# raspberrypi-testcard.net
KiCad netlist of a schematic drawn in EAGLE
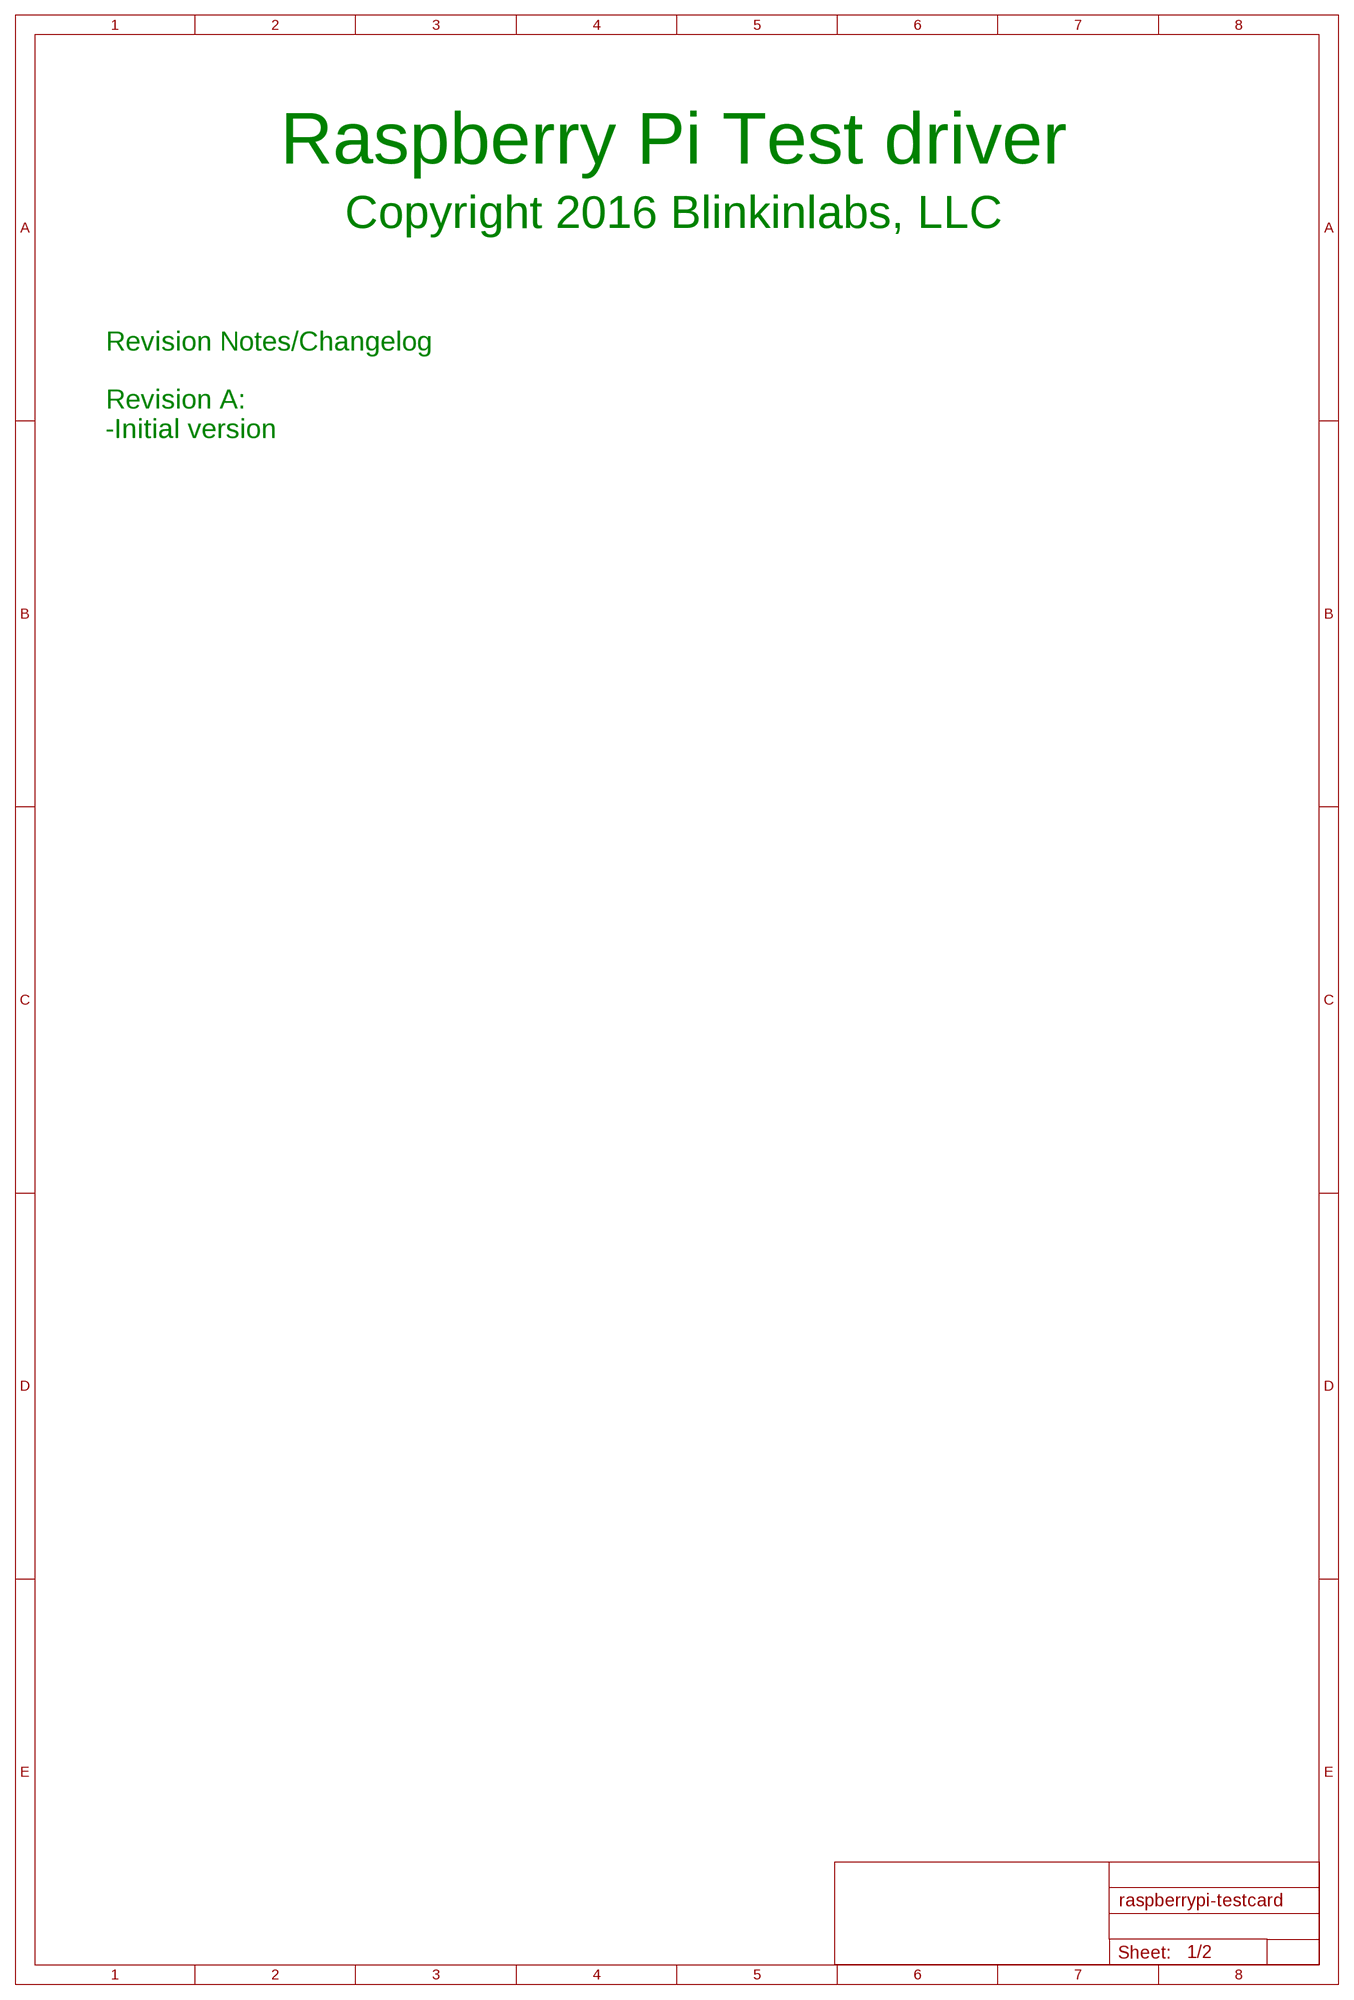
[diagram p0: schematic, sheet 1]
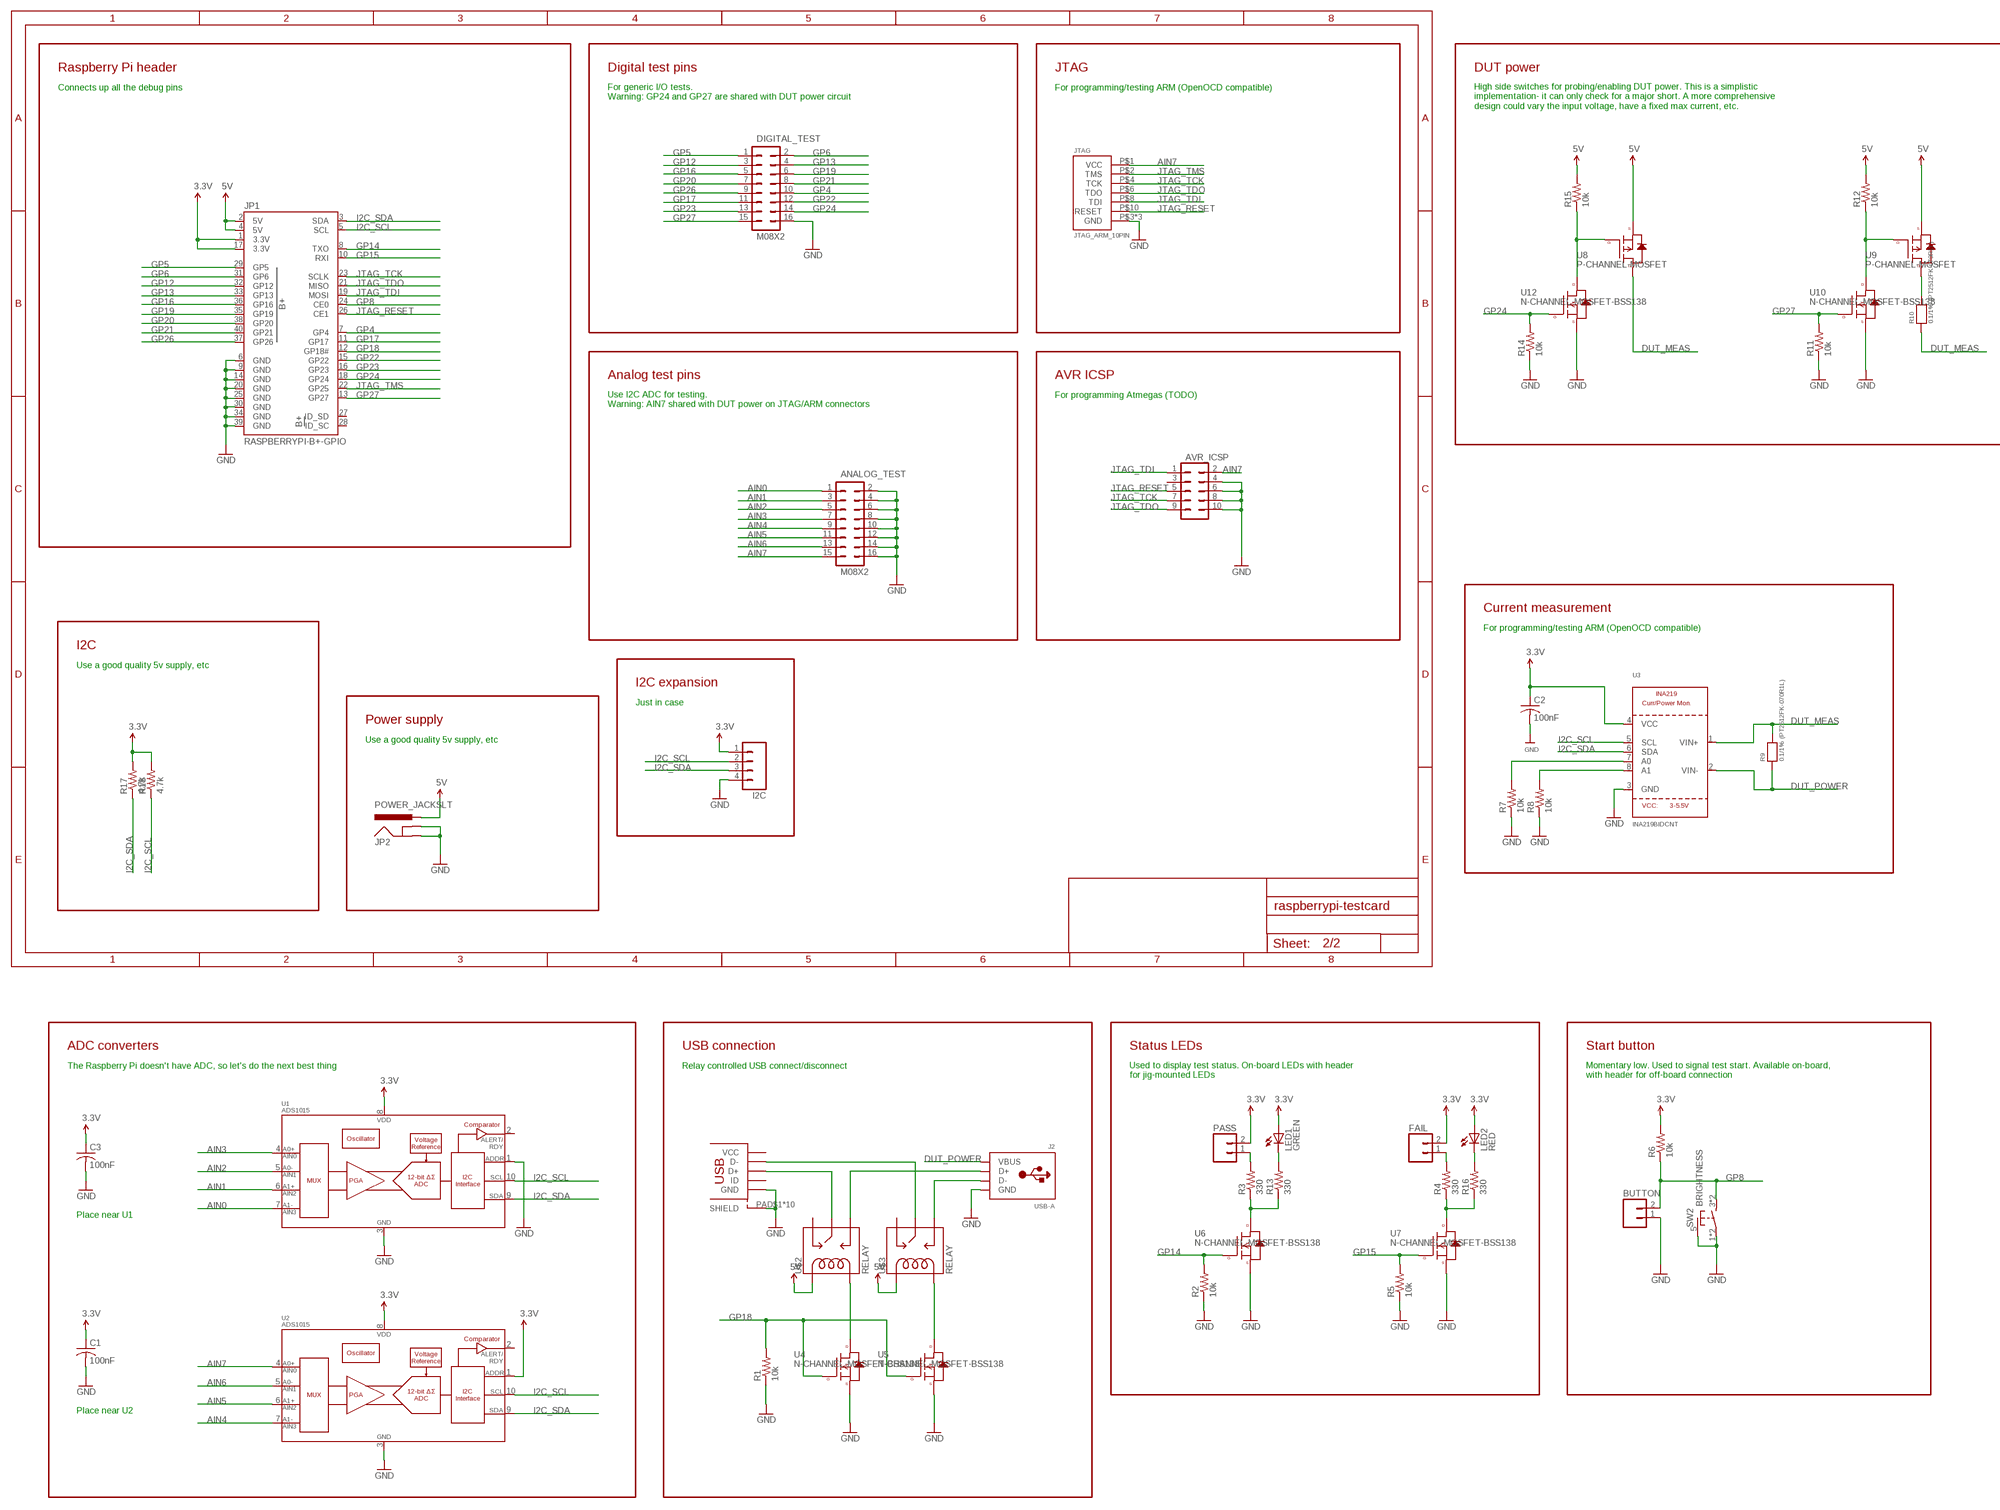
[diagram p1: schematic, sheet 2, part 1 of 2]
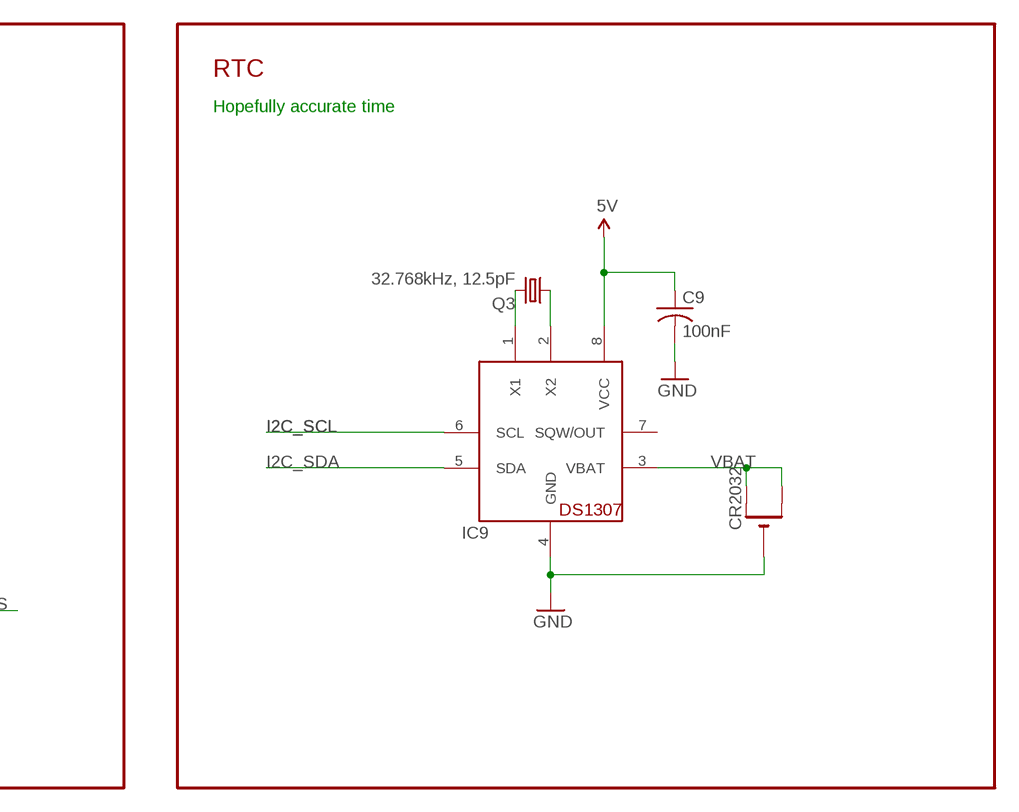
[diagram p2: schematic, sheet 2, part 2 of 2]

(export (version "E")
  (design (tool "Eeschema 10.0.6"))
  (components
    (comp (ref "ANALOG_TEST")
      (value "M08X2")
      (footprint "eagle-import:2X8")
      (libsource (lib "eagle-import") (part "M08X2"))
    )
    (comp (ref "AVR_ICSP")
      (value "M05X2PTH")
      (footprint "eagle-import:AVR_ICSP")
      (libsource (lib "eagle-import") (part "M05X2PTH"))
    )
    (comp (ref "BUTTON")
      (value "M02JST-PTH-2")
      (footprint "eagle-import:JST-2-PTH")
      (libsource (lib "eagle-import") (part "M02JST-PTH-2"))
    )
    (comp (ref "C1")
      (value "100nF")
      (footprint "eagle-import:C0402")
      (libsource (lib "eagle-import") (part "C-USC0402"))
    )
    (comp (ref "C2")
      (value "100nF")
      (footprint "eagle-import:C0402")
      (libsource (lib "eagle-import") (part "C-USC0402"))
    )
    (comp (ref "C3")
      (value "100nF")
      (footprint "eagle-import:C0402")
      (libsource (lib "eagle-import") (part "C-USC0402"))
    )
    (comp (ref "C9")
      (value "100nF")
      (footprint "eagle-import:C0402K")
      (libsource (lib "eagle-import") (part "C-USC0402K"))
    )
    (comp (ref "CR2032")
      (value "CR2032SMT")
      (footprint "eagle-import:CR2032-SMD")
      (libsource (lib "eagle-import") (part "CR2032SMT"))
    )
    (comp (ref "DIGITAL_TEST")
      (value "M08X2")
      (footprint "eagle-import:2X8")
      (libsource (lib "eagle-import") (part "M08X2"))
    )
    (comp (ref "FAIL")
      (value "M02JST-PTH-2")
      (footprint "eagle-import:JST-2-PTH")
      (libsource (lib "eagle-import") (part "M02JST-PTH-2"))
    )
    (comp (ref "I2C")
      (value "M04PTH")
      (footprint "eagle-import:1X04")
      (libsource (lib "eagle-import") (part "M04PTH"))
    )
    (comp (ref "IC9")
      (value "DS1307SO08")
      (footprint "eagle-import:SO08-150")
      (libsource (lib "eagle-import") (part "DS1307SO08"))
    )
    (comp (ref "J1")
      (value "USB_MICROSMT+THRUHULE")
      (footprint "eagle-import:USB_MICRO_THRUHOLE")
      (libsource (lib "eagle-import") (part "USB_MICROSMT+THRUHULE"))
    )
    (comp (ref "J2")
      (value "USB-A")
      (footprint "eagle-import:MOLEX_480371000")
      (libsource (lib "eagle-import") (part "USB-A"))
    )
    (comp (ref "JP1")
      (value "RASPBERRYPI-B+-GPIO")
      (footprint "eagle-import:2X20-SHROUDED")
      (libsource (lib "eagle-import") (part "RASPBERRYPI-B+-GPIO"))
    )
    (comp (ref "JP2")
      (value "POWER_JACKSLT")
      (footprint "eagle-import:POWER_JACK_SLOT")
      (libsource (lib "eagle-import") (part "POWER_JACKSLT"))
    )
    (comp (ref "JTAG")
      (value "JTAG_ARM_10PIN")
      (footprint "eagle-import:2X05-1.27MM-SMD")
      (libsource (lib "eagle-import") (part "JTAG_ARM_10PIN"))
    )
    (comp (ref "LED1")
      (value "GREEN")
      (footprint "eagle-import:CHIP-LED0805")
      (libsource (lib "eagle-import") (part "LEDCHIP-LED0805"))
    )
    (comp (ref "LED2")
      (value "RED")
      (footprint "eagle-import:CHIP-LED0805")
      (libsource (lib "eagle-import") (part "LEDCHIP-LED0805"))
    )
    (comp (ref "PASS")
      (value "M02JST-PTH-2")
      (footprint "eagle-import:JST-2-PTH")
      (libsource (lib "eagle-import") (part "M02JST-PTH-2"))
    )
    (comp (ref "Q3")
      (value "32.768kHz, 12.5pF")
      (footprint "eagle-import:TC26H")
      (libsource (lib "eagle-import") (part "CRYSTALTC26H"))
    )
    (comp (ref "R1")
      (value "10k")
      (footprint "eagle-import:R0402")
      (libsource (lib "eagle-import") (part "R-US_R0402"))
    )
    (comp (ref "R2")
      (value "10k")
      (footprint "eagle-import:R0402")
      (libsource (lib "eagle-import") (part "R-US_R0402"))
    )
    (comp (ref "R3")
      (value "330")
      (footprint "eagle-import:R0402")
      (libsource (lib "eagle-import") (part "R-US_R0402"))
    )
    (comp (ref "R4")
      (value "330")
      (footprint "eagle-import:R0402")
      (libsource (lib "eagle-import") (part "R-US_R0402"))
    )
    (comp (ref "R5")
      (value "10k")
      (footprint "eagle-import:R0402")
      (libsource (lib "eagle-import") (part "R-US_R0402"))
    )
    (comp (ref "R6")
      (value "10k")
      (footprint "eagle-import:R0402")
      (libsource (lib "eagle-import") (part "R-US_R0402"))
    )
    (comp (ref "R7")
      (value "10k")
      (footprint "eagle-import:R0402")
      (libsource (lib "eagle-import") (part "R-US_R0402"))
    )
    (comp (ref "R8")
      (value "10k")
      (footprint "eagle-import:R0402")
      (libsource (lib "eagle-import") (part "R-US_R0402"))
    )
    (comp (ref "R9")
      (value "0.1/1% (PT2512FK-070R1L)")
      (footprint "eagle-import:2512")
      (libsource (lib "eagle-import") (part "RESISTOR2512"))
    )
    (comp (ref "R10")
      (value "0.1/1% (PT2512FK-070R1L)")
      (footprint "eagle-import:2512")
      (libsource (lib "eagle-import") (part "RESISTOR2512"))
    )
    (comp (ref "R11")
      (value "10k")
      (footprint "eagle-import:R0402")
      (libsource (lib "eagle-import") (part "R-US_R0402"))
    )
    (comp (ref "R12")
      (value "10k")
      (footprint "eagle-import:R0402")
      (libsource (lib "eagle-import") (part "R-US_R0402"))
    )
    (comp (ref "R13")
      (value "330")
      (footprint "eagle-import:R0402")
      (libsource (lib "eagle-import") (part "R-US_R0402"))
    )
    (comp (ref "R14")
      (value "10k")
      (footprint "eagle-import:R0402")
      (libsource (lib "eagle-import") (part "R-US_R0402"))
    )
    (comp (ref "R15")
      (value "10k")
      (footprint "eagle-import:R0402")
      (libsource (lib "eagle-import") (part "R-US_R0402"))
    )
    (comp (ref "R16")
      (value "330")
      (footprint "eagle-import:R0402")
      (libsource (lib "eagle-import") (part "R-US_R0402"))
    )
    (comp (ref "R17")
      (value "4.7k")
      (footprint "eagle-import:R0402")
      (libsource (lib "eagle-import") (part "R-US_R0402"))
    )
    (comp (ref "R18")
      (value "4.7k")
      (footprint "eagle-import:R0402")
      (libsource (lib "eagle-import") (part "R-US_R0402"))
    )
    (comp (ref "SW2")
      (value "BRIGHTNESS")
      (footprint "eagle-import:TD-07XB")
      (libsource (lib "eagle-import") (part "BUTTON_MOMENTARY_GROUND"))
    )
    (comp (ref "U$2")
      (value "RELAY")
      (footprint "eagle-import:RELAY_HK23F-5V")
      (libsource (lib "eagle-import") (part "RELAY"))
    )
    (comp (ref "U$3")
      (value "RELAY")
      (footprint "eagle-import:RELAY_HK23F-5V")
      (libsource (lib "eagle-import") (part "RELAY"))
    )
    (comp (ref "U1")
      (value "ADS1015")
      (footprint "eagle-import:MSOP10")
      (libsource (lib "eagle-import") (part "ADS1015"))
    )
    (comp (ref "U2")
      (value "ADS1015")
      (footprint "eagle-import:MSOP10")
      (libsource (lib "eagle-import") (part "ADS1015"))
    )
    (comp (ref "U3")
      (value "INA219BIDCNT")
      (footprint "eagle-import:SOT23-8")
      (libsource (lib "eagle-import") (part "INA219"))
    )
    (comp (ref "U4")
      (value "N-CHANNEL-MOSFET-BSS138")
      (footprint "eagle-import:SOT23-3")
      (libsource (lib "eagle-import") (part "N-CHANNEL-MOSFET-BSS138"))
    )
    (comp (ref "U5")
      (value "N-CHANNEL-MOSFET-BSS138")
      (footprint "eagle-import:SOT23-3")
      (libsource (lib "eagle-import") (part "N-CHANNEL-MOSFET-BSS138"))
    )
    (comp (ref "U6")
      (value "N-CHANNEL-MOSFET-BSS138")
      (footprint "eagle-import:SOT23-3")
      (libsource (lib "eagle-import") (part "N-CHANNEL-MOSFET-BSS138"))
    )
    (comp (ref "U7")
      (value "N-CHANNEL-MOSFET-BSS138")
      (footprint "eagle-import:SOT23-3")
      (libsource (lib "eagle-import") (part "N-CHANNEL-MOSFET-BSS138"))
    )
    (comp (ref "U8")
      (value "P-CHANNEL-MOSFET")
      (footprint "eagle-import:SOT23-3")
      (libsource (lib "eagle-import") (part "P-CHANNEL-MOSFET"))
    )
    (comp (ref "U9")
      (value "P-CHANNEL-MOSFET")
      (footprint "eagle-import:SOT23-3")
      (libsource (lib "eagle-import") (part "P-CHANNEL-MOSFET"))
    )
    (comp (ref "U10")
      (value "N-CHANNEL-MOSFET-BSS138")
      (footprint "eagle-import:SOT23-3")
      (libsource (lib "eagle-import") (part "N-CHANNEL-MOSFET-BSS138"))
    )
    (comp (ref "U12")
      (value "N-CHANNEL-MOSFET-BSS138")
      (footprint "eagle-import:SOT23-3")
      (libsource (lib "eagle-import") (part "N-CHANNEL-MOSFET-BSS138"))
    )
  )
  (nets
    (net (code "1") (name "3.3V") (class "Default")
      (node (ref "C1") (pin "1") (pinfunction "1_1") (pintype "passive"))
      (node (ref "C2") (pin "1") (pinfunction "1_1") (pintype "passive"))
      (node (ref "C3") (pin "1") (pinfunction "1_1") (pintype "passive"))
      (node (ref "FAIL") (pin "2") (pinfunction "2_2") (pintype "passive"))
      (node (ref "I2C") (pin "1") (pinfunction "1_1") (pintype "passive"))
      (node (ref "JP1") (pin "1") (pinfunction "3.3V_1") (pintype "power_in"))
      (node (ref "JP1") (pin "17") (pinfunction "3.3V_17") (pintype "power_in"))
      (node (ref "LED1") (pin "A") (pinfunction "A_A") (pintype "passive"))
      (node (ref "LED2") (pin "A") (pinfunction "A_A") (pintype "passive"))
      (node (ref "PASS") (pin "2") (pinfunction "2_2") (pintype "passive"))
      (node (ref "R17") (pin "2") (pinfunction "2_2") (pintype "passive"))
      (node (ref "R18") (pin "2") (pinfunction "2_2") (pintype "passive"))
      (node (ref "R6") (pin "2") (pinfunction "2_2") (pintype "passive"))
      (node (ref "U1") (pin "8") (pinfunction "VDD_8") (pintype "bidirectional"))
      (node (ref "U2") (pin "1") (pinfunction "ADDR_1") (pintype "bidirectional"))
      (node (ref "U2") (pin "8") (pinfunction "VDD_8") (pintype "bidirectional"))
      (node (ref "U3") (pin "4") (pinfunction "VCC_4") (pintype "bidirectional"))
    )
    (net (code "2") (name "5V") (class "Default")
      (node (ref "C9") (pin "1") (pinfunction "1_1") (pintype "passive"))
      (node (ref "IC9") (pin "8") (pinfunction "VCC_8") (pintype "power_in"))
      (node (ref "JP1") (pin "2") (pinfunction "5V_2") (pintype "power_in"))
      (node (ref "JP1") (pin "4") (pinfunction "5V_4") (pintype "power_in"))
      (node (ref "JP2") (pin "PWR") (pinfunction "PWR_PWR") (pintype "bidirectional"))
      (node (ref "R12") (pin "2") (pinfunction "2_2") (pintype "passive"))
      (node (ref "R15") (pin "2") (pinfunction "2_2") (pintype "passive"))
      (node (ref "U$2") (pin "P$2") (pinfunction "COIL1_P$2") (pintype "bidirectional"))
      (node (ref "U$3") (pin "P$2") (pinfunction "COIL1_P$2") (pintype "bidirectional"))
      (node (ref "U8") (pin "2") (pinfunction "S_2") (pintype "passive"))
      (node (ref "U9") (pin "2") (pinfunction "S_2") (pintype "passive"))
    )
    (net (code "3") (name "AIN0") (class "Default")
      (node (ref "ANALOG_TEST") (pin "1") (pinfunction "1_1") (pintype "passive"))
      (node (ref "U1") (pin "7") (pinfunction "AIN3_7") (pintype "bidirectional"))
    )
    (net (code "4") (name "AIN1") (class "Default")
      (node (ref "ANALOG_TEST") (pin "3") (pinfunction "3_3") (pintype "passive"))
      (node (ref "U1") (pin "6") (pinfunction "AIN2_6") (pintype "bidirectional"))
    )
    (net (code "5") (name "AIN2") (class "Default")
      (node (ref "ANALOG_TEST") (pin "5") (pinfunction "5_5") (pintype "passive"))
      (node (ref "U1") (pin "5") (pinfunction "AIN1_5") (pintype "bidirectional"))
    )
    (net (code "6") (name "AIN3") (class "Default")
      (node (ref "ANALOG_TEST") (pin "7") (pinfunction "7_7") (pintype "passive"))
      (node (ref "U1") (pin "4") (pinfunction "AIN0_4") (pintype "bidirectional"))
    )
    (net (code "7") (name "AIN4") (class "Default")
      (node (ref "ANALOG_TEST") (pin "9") (pinfunction "9_9") (pintype "passive"))
      (node (ref "U2") (pin "7") (pinfunction "AIN3_7") (pintype "bidirectional"))
    )
    (net (code "8") (name "AIN5") (class "Default")
      (node (ref "ANALOG_TEST") (pin "11") (pinfunction "11_11") (pintype "passive"))
      (node (ref "U2") (pin "6") (pinfunction "AIN2_6") (pintype "bidirectional"))
    )
    (net (code "9") (name "AIN6") (class "Default")
      (node (ref "ANALOG_TEST") (pin "13") (pinfunction "13_13") (pintype "passive"))
      (node (ref "U2") (pin "5") (pinfunction "AIN1_5") (pintype "bidirectional"))
    )
    (net (code "10") (name "AIN7") (class "Default")
      (node (ref "ANALOG_TEST") (pin "15") (pinfunction "15_15") (pintype "passive"))
      (node (ref "AVR_ICSP") (pin "2") (pinfunction "2_2") (pintype "passive"))
      (node (ref "JTAG") (pin "P$1") (pinfunction "VCC_P$1") (pintype "power_in"))
      (node (ref "U2") (pin "4") (pinfunction "AIN0_4") (pintype "bidirectional"))
    )
    (net (code "11") (name "DUT_MEAS") (class "Default")
      (node (ref "R10") (pin "1") (pinfunction "1_1") (pintype "passive"))
      (node (ref "R9") (pin "2") (pinfunction "2_2") (pintype "passive"))
      (node (ref "U3") (pin "1") (pinfunction "VIN+_1") (pintype "bidirectional"))
      (node (ref "U8") (pin "3") (pinfunction "D_3") (pintype "passive"))
    )
    (net (code "12") (name "DUT_POWER") (class "Default")
      (node (ref "J2") (pin "1") (pinfunction "VBUS_1") (pintype "power_in"))
      (node (ref "R9") (pin "1") (pinfunction "1_1") (pintype "passive"))
      (node (ref "U3") (pin "2") (pinfunction "VIN-_2") (pintype "bidirectional"))
    )
    (net (code "13") (name "GND") (class "Default")
      (node (ref "ANALOG_TEST") (pin "10") (pinfunction "10_10") (pintype "passive"))
      (node (ref "ANALOG_TEST") (pin "12") (pinfunction "12_12") (pintype "passive"))
      (node (ref "ANALOG_TEST") (pin "14") (pinfunction "14_14") (pintype "passive"))
      (node (ref "ANALOG_TEST") (pin "16") (pinfunction "16_16") (pintype "passive"))
      (node (ref "ANALOG_TEST") (pin "2") (pinfunction "2_2") (pintype "passive"))
      (node (ref "ANALOG_TEST") (pin "4") (pinfunction "4_4") (pintype "passive"))
      (node (ref "ANALOG_TEST") (pin "6") (pinfunction "6_6") (pintype "passive"))
      (node (ref "ANALOG_TEST") (pin "8") (pinfunction "8_8") (pintype "passive"))
      (node (ref "AVR_ICSP") (pin "10") (pinfunction "10_10") (pintype "passive"))
      (node (ref "AVR_ICSP") (pin "4") (pinfunction "4_4") (pintype "passive"))
      (node (ref "AVR_ICSP") (pin "6") (pinfunction "6_6") (pintype "passive"))
      (node (ref "AVR_ICSP") (pin "8") (pinfunction "8_8") (pintype "passive"))
      (node (ref "BUTTON") (pin "1") (pinfunction "1_1") (pintype "passive"))
      (node (ref "C1") (pin "2") (pinfunction "2_2") (pintype "passive"))
      (node (ref "C2") (pin "2") (pinfunction "2_2") (pintype "passive"))
      (node (ref "C3") (pin "2") (pinfunction "2_2") (pintype "passive"))
      (node (ref "C9") (pin "2") (pinfunction "2_2") (pintype "passive"))
      (node (ref "CR2032") (pin "-") (pinfunction "-_-") (pintype "passive"))
      (node (ref "DIGITAL_TEST") (pin "16") (pinfunction "16_16") (pintype "passive"))
      (node (ref "I2C") (pin "4") (pinfunction "4_4") (pintype "passive"))
      (node (ref "IC9") (pin "4") (pinfunction "GND_4") (pintype "power_in"))
      (node (ref "J1") (pin "PAD$1") (pinfunction "SHIELD_PAD$1") (pintype "bidirectional"))
      (node (ref "J1") (pin "PAD$10") (pinfunction "SHIELD_PAD$10") (pintype "bidirectional"))
      (node (ref "J1") (pin "PAD$2") (pinfunction "SHIELD_PAD$2") (pintype "bidirectional"))
      (node (ref "J1") (pin "PAD$3") (pinfunction "SHIELD_PAD$3") (pintype "bidirectional"))
      (node (ref "J1") (pin "PAD$4") (pinfunction "SHIELD_PAD$4") (pintype "bidirectional"))
      (node (ref "J1") (pin "PAD$5") (pinfunction "SHIELD_PAD$5") (pintype "bidirectional"))
      (node (ref "J1") (pin "PAD$6") (pinfunction "SHIELD_PAD$6") (pintype "bidirectional"))
      (node (ref "J1") (pin "PAD$7") (pinfunction "SHIELD_PAD$7") (pintype "bidirectional"))
      (node (ref "J1") (pin "PAD$8") (pinfunction "SHIELD_PAD$8") (pintype "bidirectional"))
      (node (ref "J1") (pin "PAD$9") (pinfunction "SHIELD_PAD$9") (pintype "bidirectional"))
      (node (ref "J1") (pin "PIN$5") (pinfunction "GND_PIN$5") (pintype "bidirectional"))
      (node (ref "J2") (pin "4") (pinfunction "GND_4") (pintype "power_in"))
      (node (ref "JP1") (pin "14") (pinfunction "GND_14") (pintype "power_in"))
      (node (ref "JP1") (pin "20") (pinfunction "GND_20") (pintype "power_in"))
      (node (ref "JP1") (pin "25") (pinfunction "GND_25") (pintype "power_in"))
      (node (ref "JP1") (pin "30") (pinfunction "GND_30") (pintype "power_in"))
      (node (ref "JP1") (pin "34") (pinfunction "GND_34") (pintype "power_in"))
      (node (ref "JP1") (pin "39") (pinfunction "GND_39") (pintype "power_in"))
      (node (ref "JP1") (pin "6") (pinfunction "GND_6") (pintype "power_in"))
      (node (ref "JP1") (pin "9") (pinfunction "GND_9") (pintype "power_in"))
      (node (ref "JP2") (pin "GND@1") (pinfunction "GNDBREAK_GND@1") (pintype "bidirectional"))
      (node (ref "JP2") (pin "GND@2") (pinfunction "GND_GND@2") (pintype "bidirectional"))
      (node (ref "JTAG") (pin "P$3") (pinfunction "GND_P$3") (pintype "power_in"))
      (node (ref "JTAG") (pin "P$5") (pinfunction "GND_P$5") (pintype "power_in"))
      (node (ref "JTAG") (pin "P$9") (pinfunction "GND_P$9") (pintype "power_in"))
      (node (ref "R1") (pin "1") (pinfunction "1_1") (pintype "passive"))
      (node (ref "R11") (pin "1") (pinfunction "1_1") (pintype "passive"))
      (node (ref "R14") (pin "1") (pinfunction "1_1") (pintype "passive"))
      (node (ref "R2") (pin "1") (pinfunction "1_1") (pintype "passive"))
      (node (ref "R5") (pin "1") (pinfunction "1_1") (pintype "passive"))
      (node (ref "R7") (pin "1") (pinfunction "1_1") (pintype "passive"))
      (node (ref "R8") (pin "1") (pinfunction "1_1") (pintype "passive"))
      (node (ref "SW2") (pin "1") (pinfunction "P_1") (pintype "passive"))
      (node (ref "SW2") (pin "2") (pinfunction "P_2") (pintype "passive"))
      (node (ref "SW2") (pin "5") (pinfunction "SHIELD_5") (pintype "passive"))
      (node (ref "U1") (pin "1") (pinfunction "ADDR_1") (pintype "bidirectional"))
      (node (ref "U1") (pin "3") (pinfunction "VSS_3") (pintype "bidirectional"))
      (node (ref "U10") (pin "2") (pinfunction "S_2") (pintype "passive"))
      (node (ref "U12") (pin "2") (pinfunction "S_2") (pintype "passive"))
      (node (ref "U2") (pin "3") (pinfunction "VSS_3") (pintype "bidirectional"))
      (node (ref "U3") (pin "3") (pinfunction "GND_3") (pintype "bidirectional"))
      (node (ref "U4") (pin "2") (pinfunction "S_2") (pintype "passive"))
      (node (ref "U5") (pin "2") (pinfunction "S_2") (pintype "passive"))
      (node (ref "U6") (pin "2") (pinfunction "S_2") (pintype "passive"))
      (node (ref "U7") (pin "2") (pinfunction "S_2") (pintype "passive"))
    )
    (net (code "14") (name "GP4") (class "Default")
      (node (ref "DIGITAL_TEST") (pin "10") (pinfunction "10_10") (pintype "passive"))
      (node (ref "JP1") (pin "7") (pinfunction "GP4_7") (pintype "bidirectional"))
    )
    (net (code "15") (name "GP5") (class "Default")
      (node (ref "DIGITAL_TEST") (pin "1") (pinfunction "1_1") (pintype "passive"))
      (node (ref "JP1") (pin "29") (pinfunction "GP5_29") (pintype "bidirectional"))
    )
    (net (code "16") (name "GP6") (class "Default")
      (node (ref "DIGITAL_TEST") (pin "2") (pinfunction "2_2") (pintype "passive"))
      (node (ref "JP1") (pin "31") (pinfunction "GP6_31") (pintype "bidirectional"))
    )
    (net (code "17") (name "GP8") (class "Default")
      (node (ref "BUTTON") (pin "2") (pinfunction "2_2") (pintype "passive"))
      (node (ref "JP1") (pin "24") (pinfunction "CE0_24") (pintype "output"))
      (node (ref "R6") (pin "1") (pinfunction "1_1") (pintype "passive"))
      (node (ref "SW2") (pin "3") (pinfunction "S_3") (pintype "passive"))
      (node (ref "SW2") (pin "4") (pinfunction "S_4") (pintype "passive"))
    )
    (net (code "18") (name "GP12") (class "Default")
      (node (ref "DIGITAL_TEST") (pin "3") (pinfunction "3_3") (pintype "passive"))
      (node (ref "JP1") (pin "32") (pinfunction "GP12_32") (pintype "bidirectional"))
    )
    (net (code "19") (name "GP13") (class "Default")
      (node (ref "DIGITAL_TEST") (pin "4") (pinfunction "4_4") (pintype "passive"))
      (node (ref "JP1") (pin "33") (pinfunction "GP13_33") (pintype "bidirectional"))
    )
    (net (code "20") (name "GP14") (class "Default")
      (node (ref "JP1") (pin "8") (pinfunction "TXO_8") (pintype "output"))
      (node (ref "R2") (pin "2") (pinfunction "2_2") (pintype "passive"))
      (node (ref "U6") (pin "1") (pinfunction "G_1") (pintype "passive"))
    )
    (net (code "21") (name "GP15") (class "Default")
      (node (ref "JP1") (pin "10") (pinfunction "RXI_10") (pintype "input"))
      (node (ref "R5") (pin "2") (pinfunction "2_2") (pintype "passive"))
      (node (ref "U7") (pin "1") (pinfunction "G_1") (pintype "passive"))
    )
    (net (code "22") (name "GP16") (class "Default")
      (node (ref "DIGITAL_TEST") (pin "5") (pinfunction "5_5") (pintype "passive"))
      (node (ref "JP1") (pin "36") (pinfunction "GP16_36") (pintype "bidirectional"))
    )
    (net (code "23") (name "GP17") (class "Default")
      (node (ref "DIGITAL_TEST") (pin "11") (pinfunction "11_11") (pintype "passive"))
      (node (ref "JP1") (pin "11") (pinfunction "GP17_11") (pintype "bidirectional"))
    )
    (net (code "24") (name "GP18") (class "Default")
      (node (ref "JP1") (pin "12") (pinfunction "GP18#_12") (pintype "bidirectional"))
      (node (ref "R1") (pin "2") (pinfunction "2_2") (pintype "passive"))
      (node (ref "U4") (pin "1") (pinfunction "G_1") (pintype "passive"))
      (node (ref "U5") (pin "1") (pinfunction "G_1") (pintype "passive"))
    )
    (net (code "25") (name "GP19") (class "Default")
      (node (ref "DIGITAL_TEST") (pin "6") (pinfunction "6_6") (pintype "passive"))
      (node (ref "JP1") (pin "35") (pinfunction "GP19_35") (pintype "bidirectional"))
    )
    (net (code "26") (name "GP20") (class "Default")
      (node (ref "DIGITAL_TEST") (pin "7") (pinfunction "7_7") (pintype "passive"))
      (node (ref "JP1") (pin "38") (pinfunction "GP20_38") (pintype "bidirectional"))
    )
    (net (code "27") (name "GP21") (class "Default")
      (node (ref "DIGITAL_TEST") (pin "8") (pinfunction "8_8") (pintype "passive"))
      (node (ref "JP1") (pin "40") (pinfunction "GP21_40") (pintype "bidirectional"))
    )
    (net (code "28") (name "GP22") (class "Default")
      (node (ref "DIGITAL_TEST") (pin "12") (pinfunction "12_12") (pintype "passive"))
      (node (ref "JP1") (pin "15") (pinfunction "GP22_15") (pintype "bidirectional"))
    )
    (net (code "29") (name "GP23") (class "Default")
      (node (ref "DIGITAL_TEST") (pin "13") (pinfunction "13_13") (pintype "passive"))
      (node (ref "JP1") (pin "16") (pinfunction "GP23_16") (pintype "bidirectional"))
    )
    (net (code "30") (name "GP24") (class "Default")
      (node (ref "DIGITAL_TEST") (pin "14") (pinfunction "14_14") (pintype "passive"))
      (node (ref "JP1") (pin "18") (pinfunction "GP24_18") (pintype "bidirectional"))
      (node (ref "R14") (pin "2") (pinfunction "2_2") (pintype "passive"))
      (node (ref "U12") (pin "1") (pinfunction "G_1") (pintype "passive"))
    )
    (net (code "31") (name "GP26") (class "Default")
      (node (ref "DIGITAL_TEST") (pin "9") (pinfunction "9_9") (pintype "passive"))
      (node (ref "JP1") (pin "37") (pinfunction "GP26_37") (pintype "bidirectional"))
    )
    (net (code "32") (name "GP27") (class "Default")
      (node (ref "DIGITAL_TEST") (pin "15") (pinfunction "15_15") (pintype "passive"))
      (node (ref "JP1") (pin "13") (pinfunction "GP27_13") (pintype "bidirectional"))
      (node (ref "R11") (pin "2") (pinfunction "2_2") (pintype "passive"))
      (node (ref "U10") (pin "1") (pinfunction "G_1") (pintype "passive"))
    )
    (net (code "33") (name "I2C_SCL") (class "Default")
      (node (ref "I2C") (pin "2") (pinfunction "2_2") (pintype "passive"))
      (node (ref "IC9") (pin "6") (pinfunction "SCL_6") (pintype "bidirectional"))
      (node (ref "JP1") (pin "5") (pinfunction "SCL_5") (pintype "bidirectional"))
      (node (ref "R18") (pin "1") (pinfunction "1_1") (pintype "passive"))
      (node (ref "U1") (pin "10") (pinfunction "SCL_10") (pintype "bidirectional"))
      (node (ref "U2") (pin "10") (pinfunction "SCL_10") (pintype "bidirectional"))
      (node (ref "U3") (pin "5") (pinfunction "SCL_5") (pintype "bidirectional"))
    )
    (net (code "34") (name "I2C_SDA") (class "Default")
      (node (ref "I2C") (pin "3") (pinfunction "3_3") (pintype "passive"))
      (node (ref "IC9") (pin "5") (pinfunction "SDA_5") (pintype "bidirectional"))
      (node (ref "JP1") (pin "3") (pinfunction "SDA_3") (pintype "bidirectional"))
      (node (ref "R17") (pin "1") (pinfunction "1_1") (pintype "passive"))
      (node (ref "U1") (pin "9") (pinfunction "SDA_9") (pintype "bidirectional"))
      (node (ref "U2") (pin "9") (pinfunction "SDA_9") (pintype "bidirectional"))
      (node (ref "U3") (pin "6") (pinfunction "SDA_6") (pintype "bidirectional"))
    )
    (net (code "35") (name "JTAG_RESET") (class "Default")
      (node (ref "AVR_ICSP") (pin "5") (pinfunction "5_5") (pintype "passive"))
      (node (ref "JP1") (pin "26") (pinfunction "CE1_26") (pintype "output"))
      (node (ref "JTAG") (pin "P$10") (pinfunction "RESET_P$10") (pintype "bidirectional"))
    )
    (net (code "36") (name "JTAG_TCK") (class "Default")
      (node (ref "AVR_ICSP") (pin "7") (pinfunction "7_7") (pintype "passive"))
      (node (ref "JP1") (pin "23") (pinfunction "SCLK_23") (pintype "output"))
      (node (ref "JTAG") (pin "P$4") (pinfunction "TCK_P$4") (pintype "bidirectional"))
    )
    (net (code "37") (name "JTAG_TDI") (class "Default")
      (node (ref "AVR_ICSP") (pin "1") (pinfunction "1_1") (pintype "passive"))
      (node (ref "JP1") (pin "19") (pinfunction "MOSI_19") (pintype "output"))
      (node (ref "JTAG") (pin "P$8") (pinfunction "TDI_P$8") (pintype "bidirectional"))
    )
    (net (code "38") (name "JTAG_TDO") (class "Default")
      (node (ref "AVR_ICSP") (pin "9") (pinfunction "9_9") (pintype "passive"))
      (node (ref "JP1") (pin "21") (pinfunction "MISO_21") (pintype "input"))
      (node (ref "JTAG") (pin "P$6") (pinfunction "TDO_P$6") (pintype "bidirectional"))
    )
    (net (code "39") (name "JTAG_TMS") (class "Default")
      (node (ref "JP1") (pin "22") (pinfunction "GP25_22") (pintype "bidirectional"))
      (node (ref "JTAG") (pin "P$2") (pinfunction "TMS_P$2") (pintype "bidirectional"))
    )
    (net (code "40") (name "Net-(FAIL-Pad1)") (class "Default")
      (node (ref "FAIL") (pin "1") (pinfunction "1_1") (pintype "passive"))
      (node (ref "R4") (pin "2") (pinfunction "2_2") (pintype "passive"))
    )
    (net (code "41") (name "Net-(IC9-X1)") (class "Default")
      (node (ref "IC9") (pin "1") (pinfunction "X1_1") (pintype "passive"))
      (node (ref "Q3") (pin "2") (pinfunction "2_2") (pintype "passive"))
    )
    (net (code "42") (name "Net-(IC9-X2)") (class "Default")
      (node (ref "IC9") (pin "2") (pinfunction "X2_2") (pintype "passive"))
      (node (ref "Q3") (pin "1") (pinfunction "1_1") (pintype "passive"))
    )
    (net (code "43") (name "Net-(J1-D+)") (class "Default")
      (node (ref "J1") (pin "PIN$3") (pinfunction "D+_PIN$3") (pintype "bidirectional"))
      (node (ref "U$2") (pin "P$1") (pinfunction "MAIN_P$1") (pintype "bidirectional"))
      (node (ref "U$2") (pin "P$6") (pinfunction "MAIN_P$6") (pintype "bidirectional"))
    )
    (net (code "44") (name "Net-(J1-D-)") (class "Default")
      (node (ref "J1") (pin "PIN$2") (pinfunction "D-_PIN$2") (pintype "bidirectional"))
      (node (ref "U$3") (pin "P$1") (pinfunction "MAIN_P$1") (pintype "bidirectional"))
      (node (ref "U$3") (pin "P$6") (pinfunction "MAIN_P$6") (pintype "bidirectional"))
    )
    (net (code "45") (name "Net-(J2-D+)") (class "Default")
      (node (ref "J2") (pin "3") (pinfunction "D+_3") (pintype "bidirectional"))
      (node (ref "U$2") (pin "P$3") (pinfunction "NO_P$3") (pintype "bidirectional"))
    )
    (net (code "46") (name "Net-(J2-D-)") (class "Default")
      (node (ref "J2") (pin "2") (pinfunction "D-_2") (pintype "bidirectional"))
      (node (ref "U$3") (pin "P$3") (pinfunction "NO_P$3") (pintype "bidirectional"))
    )
    (net (code "47") (name "Net-(LED1-PadC)") (class "Default")
      (node (ref "LED1") (pin "C") (pinfunction "C_C") (pintype "passive"))
      (node (ref "R13") (pin "2") (pinfunction "2_2") (pintype "passive"))
    )
    (net (code "48") (name "Net-(LED2-PadC)") (class "Default")
      (node (ref "LED2") (pin "C") (pinfunction "C_C") (pintype "passive"))
      (node (ref "R16") (pin "2") (pinfunction "2_2") (pintype "passive"))
    )
    (net (code "49") (name "Net-(PASS-Pad1)") (class "Default")
      (node (ref "PASS") (pin "1") (pinfunction "1_1") (pintype "passive"))
      (node (ref "R3") (pin "2") (pinfunction "2_2") (pintype "passive"))
    )
    (net (code "50") (name "Net-(U$2-COIL2)") (class "Default")
      (node (ref "U$2") (pin "P$5") (pinfunction "COIL2_P$5") (pintype "bidirectional"))
      (node (ref "U4") (pin "3") (pinfunction "D_3") (pintype "passive"))
    )
    (net (code "51") (name "Net-(U$3-COIL2)") (class "Default")
      (node (ref "U$3") (pin "P$5") (pinfunction "COIL2_P$5") (pintype "bidirectional"))
      (node (ref "U5") (pin "3") (pinfunction "D_3") (pintype "passive"))
    )
    (net (code "52") (name "Net-(U3-A0)") (class "Default")
      (node (ref "R7") (pin "2") (pinfunction "2_2") (pintype "passive"))
      (node (ref "U3") (pin "7") (pinfunction "A0_7") (pintype "bidirectional"))
    )
    (net (code "53") (name "Net-(U3-A1)") (class "Default")
      (node (ref "R8") (pin "2") (pinfunction "2_2") (pintype "passive"))
      (node (ref "U3") (pin "8") (pinfunction "A1_8") (pintype "bidirectional"))
    )
    (net (code "54") (name "Net-(U6-D)") (class "Default")
      (node (ref "R13") (pin "1") (pinfunction "1_1") (pintype "passive"))
      (node (ref "R3") (pin "1") (pinfunction "1_1") (pintype "passive"))
      (node (ref "U6") (pin "3") (pinfunction "D_3") (pintype "passive"))
    )
    (net (code "55") (name "Net-(U7-D)") (class "Default")
      (node (ref "R16") (pin "1") (pinfunction "1_1") (pintype "passive"))
      (node (ref "R4") (pin "1") (pinfunction "1_1") (pintype "passive"))
      (node (ref "U7") (pin "3") (pinfunction "D_3") (pintype "passive"))
    )
    (net (code "56") (name "Net-(U9-D)") (class "Default")
      (node (ref "R10") (pin "2") (pinfunction "2_2") (pintype "passive"))
      (node (ref "U9") (pin "3") (pinfunction "D_3") (pintype "passive"))
    )
    (net (code "57") (name "Net-(U10-D)") (class "Default")
      (node (ref "R12") (pin "1") (pinfunction "1_1") (pintype "passive"))
      (node (ref "U10") (pin "3") (pinfunction "D_3") (pintype "passive"))
      (node (ref "U9") (pin "1") (pinfunction "G_1") (pintype "passive"))
    )
    (net (code "58") (name "Net-(U12-D)") (class "Default")
      (node (ref "R15") (pin "1") (pinfunction "1_1") (pintype "passive"))
      (node (ref "U12") (pin "3") (pinfunction "D_3") (pintype "passive"))
      (node (ref "U8") (pin "1") (pinfunction "G_1") (pintype "passive"))
    )
    (net (code "59") (name "VBAT") (class "Default")
      (node (ref "CR2032") (pin "+$1") (pinfunction "+_+$1") (pintype "passive"))
      (node (ref "CR2032") (pin "+$2") (pinfunction "+1_+$2") (pintype "passive"))
      (node (ref "IC9") (pin "3") (pinfunction "VBAT_3") (pintype "power_in"))
    )
    (net (code "60") (name "unconnected-(AVR_ICSP-Pad3)") (class "Default")
      (node (ref "AVR_ICSP") (pin "3") (pinfunction "3_3") (pintype "passive"))
    )
    (net (code "61") (name "unconnected-(IC9-SQW{slash}OUT-Pad7)") (class "Default")
      (node (ref "IC9") (pin "7") (pinfunction "SQW/OUT_7") (pintype "bidirectional"))
    )
    (net (code "62") (name "unconnected-(J1-ID-PadPIN$4)") (class "Default")
      (node (ref "J1") (pin "PIN$4") (pinfunction "ID_PIN$4") (pintype "bidirectional"))
    )
    (net (code "63") (name "unconnected-(J1-VCC-PadPIN$1)") (class "Default")
      (node (ref "J1") (pin "PIN$1") (pinfunction "VCC_PIN$1") (pintype "bidirectional"))
    )
    (net (code "64") (name "unconnected-(JP1-ID_SC-Pad28)") (class "Default")
      (node (ref "JP1") (pin "28") (pinfunction "ID_SC_28") (pintype "bidirectional"))
    )
    (net (code "65") (name "unconnected-(JP1-ID_SD-Pad27)") (class "Default")
      (node (ref "JP1") (pin "27") (pinfunction "ID_SD_27") (pintype "bidirectional"))
    )
    (net (code "66") (name "unconnected-(U$2-NC-PadP$4)") (class "Default")
      (node (ref "U$2") (pin "P$4") (pinfunction "NC_P$4") (pintype "bidirectional"))
    )
    (net (code "67") (name "unconnected-(U$3-NC-PadP$4)") (class "Default")
      (node (ref "U$3") (pin "P$4") (pinfunction "NC_P$4") (pintype "bidirectional"))
    )
    (net (code "68") (name "unconnected-(U1-ALERT{slash}RDY-Pad2)") (class "Default")
      (node (ref "U1") (pin "2") (pinfunction "ALERT/RDY_2") (pintype "bidirectional"))
    )
    (net (code "69") (name "unconnected-(U2-ALERT{slash}RDY-Pad2)") (class "Default")
      (node (ref "U2") (pin "2") (pinfunction "ALERT/RDY_2") (pintype "bidirectional"))
    )
  )
)
